# OpenLog_ESP32.net
KiCad netlist of a schematic drawn in EAGLE
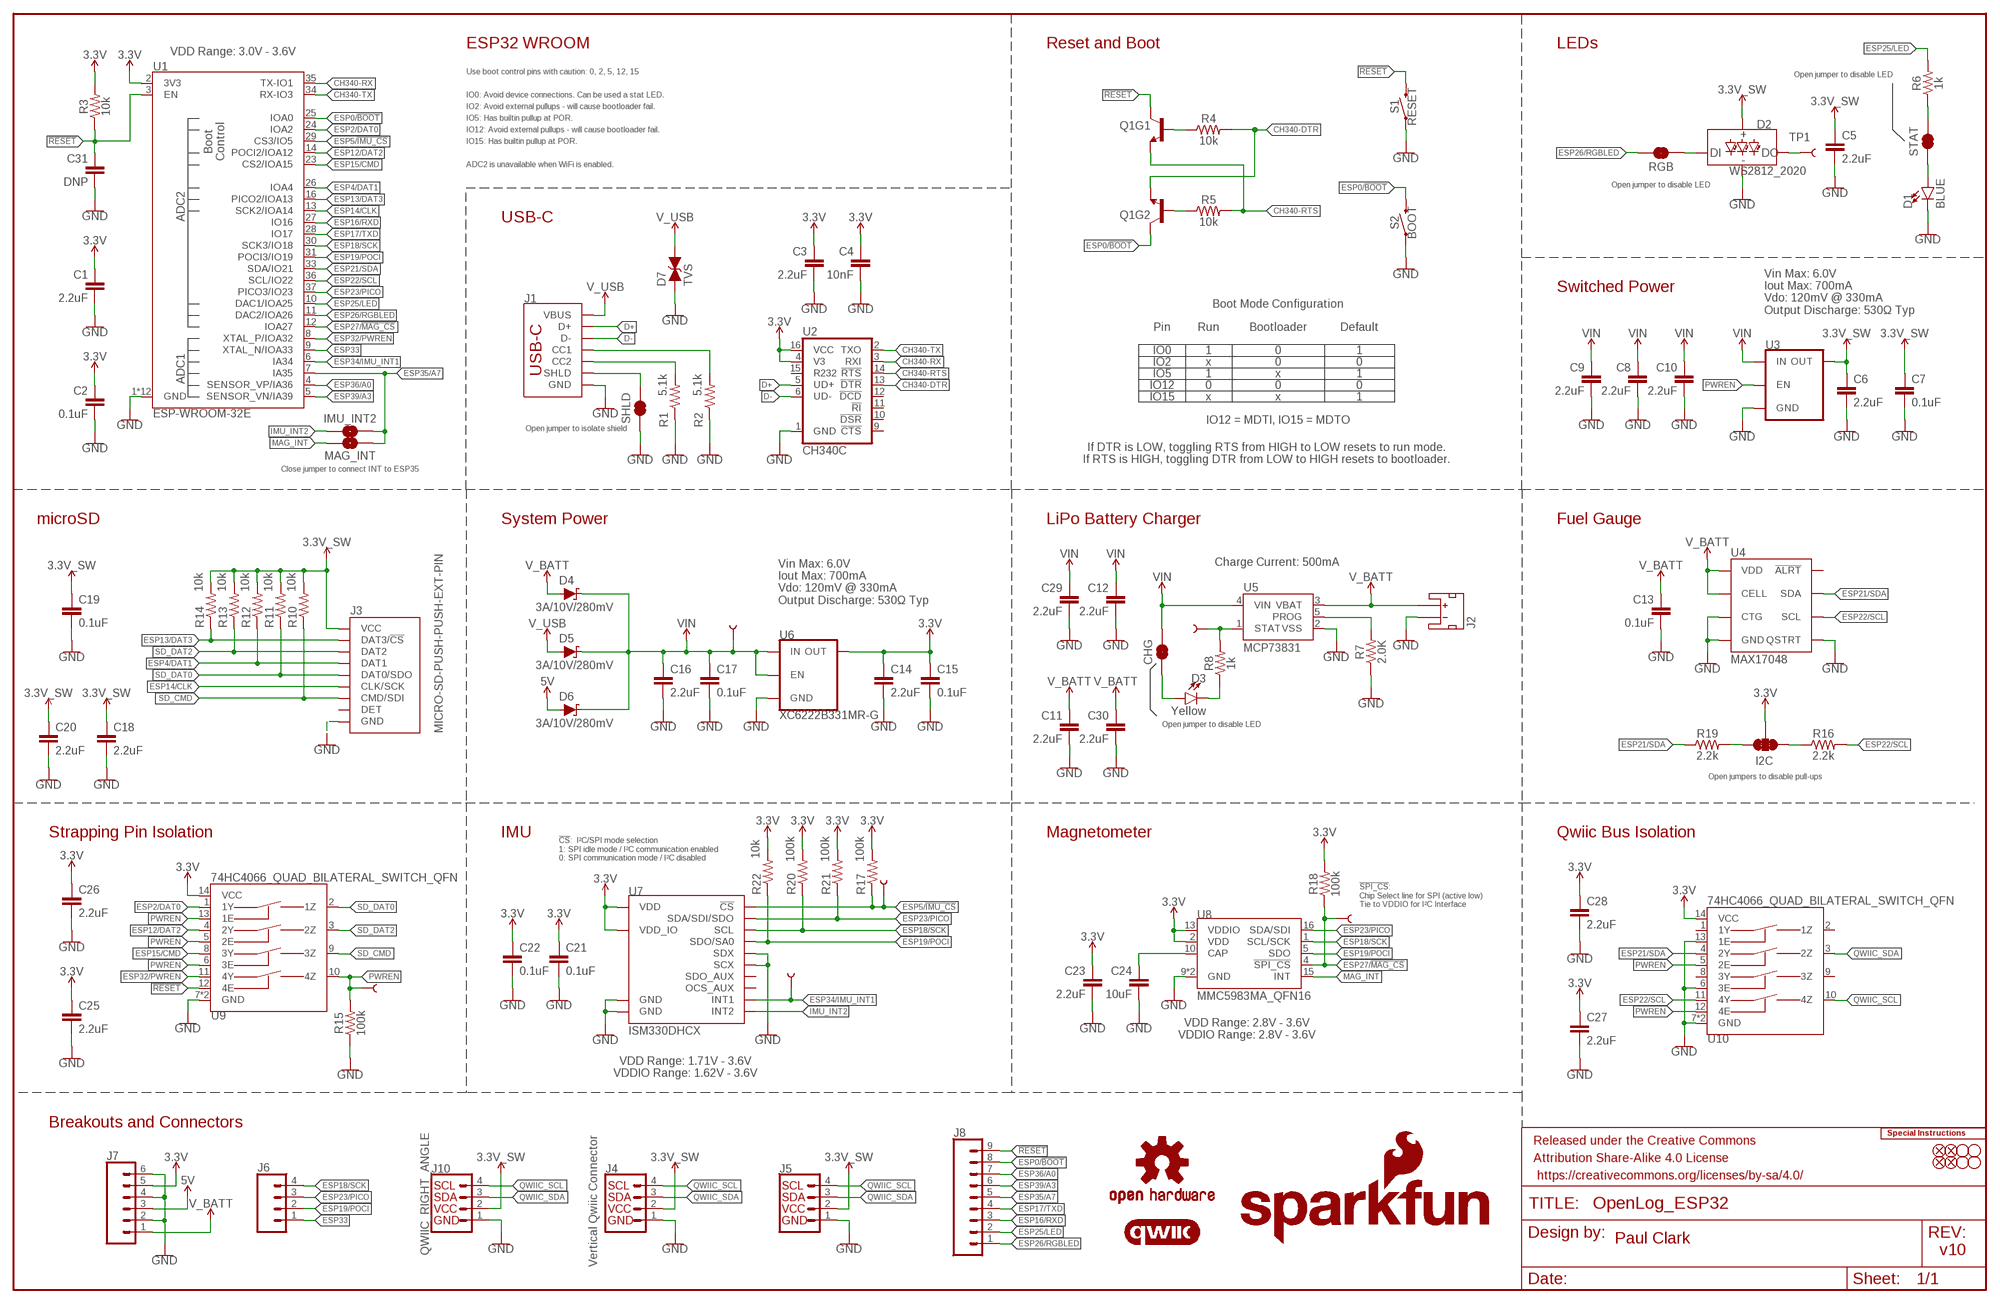
[diagram p0: schematic, sheet 1]

(export (version "E")
  (design (tool "Eeschema 10.0.6"))
  (components
    (comp (ref "C1")
      (value "2.2uF")
      (footprint "eagle-import:0402-TIGHT")
      (libsource (lib "eagle-import") (part "2.2UF-0402_TIGHT-10V-10%-X5R"))
    )
    (comp (ref "C2")
      (value "0.1uF")
      (footprint "eagle-import:0402-TIGHT")
      (libsource (lib "eagle-import") (part "0.1UF-0402T-6.3V-10%-X7R"))
    )
    (comp (ref "C3")
      (value "2.2uF")
      (footprint "eagle-import:0402-TIGHT")
      (libsource (lib "eagle-import") (part "2.2UF-0402_TIGHT-10V-10%-X5R"))
    )
    (comp (ref "C4")
      (value "10nF")
      (footprint "eagle-import:0402-TIGHT")
      (libsource (lib "eagle-import") (part "10NF-0402T-25V-10%-X7R-WE"))
    )
    (comp (ref "C5")
      (value "2.2uF")
      (footprint "eagle-import:0402-TIGHT")
      (libsource (lib "eagle-import") (part "2.2UF-0402_TIGHT-10V-10%-X5R"))
    )
    (comp (ref "C6")
      (value "2.2uF")
      (footprint "eagle-import:0402-TIGHT")
      (libsource (lib "eagle-import") (part "2.2UF-0402_TIGHT-10V-10%-X5R"))
    )
    (comp (ref "C7")
      (value "0.1uF")
      (footprint "eagle-import:0402-TIGHT")
      (libsource (lib "eagle-import") (part "0.1UF-0402T-6.3V-10%-X7R"))
    )
    (comp (ref "C8")
      (value "2.2uF")
      (footprint "eagle-import:0402-TIGHT")
      (libsource (lib "eagle-import") (part "2.2UF-0402_TIGHT-10V-10%-X5R"))
    )
    (comp (ref "C9")
      (value "2.2uF")
      (footprint "eagle-import:0402-TIGHT")
      (libsource (lib "eagle-import") (part "2.2UF-0402_TIGHT-10V-10%-X5R"))
    )
    (comp (ref "C10")
      (value "2.2uF")
      (footprint "eagle-import:0402-TIGHT")
      (libsource (lib "eagle-import") (part "2.2UF-0402_TIGHT-10V-10%-X5R"))
    )
    (comp (ref "C11")
      (value "2.2uF")
      (footprint "eagle-import:0402-TIGHT")
      (libsource (lib "eagle-import") (part "2.2UF-0402_TIGHT-10V-10%-X5R"))
    )
    (comp (ref "C12")
      (value "2.2uF")
      (footprint "eagle-import:0402-TIGHT")
      (libsource (lib "eagle-import") (part "2.2UF-0402_TIGHT-10V-10%-X5R"))
    )
    (comp (ref "C13")
      (value "0.1uF")
      (footprint "eagle-import:0402-TIGHT")
      (libsource (lib "eagle-import") (part "0.1UF-0402T-6.3V-10%-X7R"))
    )
    (comp (ref "C14")
      (value "2.2uF")
      (footprint "eagle-import:0402-TIGHT")
      (libsource (lib "eagle-import") (part "2.2UF-0402_TIGHT-10V-10%-X5R"))
    )
    (comp (ref "C15")
      (value "0.1uF")
      (footprint "eagle-import:0402-TIGHT")
      (libsource (lib "eagle-import") (part "0.1UF-0402T-6.3V-10%-X7R"))
    )
    (comp (ref "C16")
      (value "2.2uF")
      (footprint "eagle-import:0402-TIGHT")
      (libsource (lib "eagle-import") (part "2.2UF-0402_TIGHT-10V-10%-X5R"))
    )
    (comp (ref "C17")
      (value "0.1uF")
      (footprint "eagle-import:0402-TIGHT")
      (libsource (lib "eagle-import") (part "0.1UF-0402T-6.3V-10%-X7R"))
    )
    (comp (ref "C18")
      (value "2.2uF")
      (footprint "eagle-import:0402-TIGHT")
      (libsource (lib "eagle-import") (part "2.2UF-0402_TIGHT-10V-10%-X5R"))
    )
    (comp (ref "C19")
      (value "0.1uF")
      (footprint "eagle-import:0402-TIGHT")
      (libsource (lib "eagle-import") (part "0.1UF-0402T-6.3V-10%-X7R"))
    )
    (comp (ref "C20")
      (value "2.2uF")
      (footprint "eagle-import:0402-TIGHT")
      (libsource (lib "eagle-import") (part "2.2UF-0402_TIGHT-10V-10%-X5R"))
    )
    (comp (ref "C21")
      (value "0.1uF")
      (footprint "eagle-import:0402-TIGHT")
      (libsource (lib "eagle-import") (part "0.1UF-0402T-6.3V-10%-X7R"))
    )
    (comp (ref "C22")
      (value "0.1uF")
      (footprint "eagle-import:0402-TIGHT")
      (libsource (lib "eagle-import") (part "0.1UF-0402T-6.3V-10%-X7R"))
    )
    (comp (ref "C23")
      (value "2.2uF")
      (footprint "eagle-import:0402-TIGHT")
      (libsource (lib "eagle-import") (part "2.2UF-0402_TIGHT-10V-10%-X5R"))
    )
    (comp (ref "C24")
      (value "10uF")
      (footprint "eagle-import:0402-TIGHT")
      (libsource (lib "eagle-import") (part "10UF-0402T-6.3V-20%"))
    )
    (comp (ref "C25")
      (value "2.2uF")
      (footprint "eagle-import:0402-TIGHT")
      (libsource (lib "eagle-import") (part "2.2UF-0402_TIGHT-10V-10%-X5R"))
    )
    (comp (ref "C26")
      (value "2.2uF")
      (footprint "eagle-import:0402-TIGHT")
      (libsource (lib "eagle-import") (part "2.2UF-0402_TIGHT-10V-10%-X5R"))
    )
    (comp (ref "C27")
      (value "2.2uF")
      (footprint "eagle-import:0402-TIGHT")
      (libsource (lib "eagle-import") (part "2.2UF-0402_TIGHT-10V-10%-X5R"))
    )
    (comp (ref "C28")
      (value "2.2uF")
      (footprint "eagle-import:0402-TIGHT")
      (libsource (lib "eagle-import") (part "2.2UF-0402_TIGHT-10V-10%-X5R"))
    )
    (comp (ref "C29")
      (value "2.2uF")
      (footprint "eagle-import:0402-TIGHT")
      (libsource (lib "eagle-import") (part "2.2UF-0402_TIGHT-10V-10%-X5R"))
    )
    (comp (ref "C30")
      (value "2.2uF")
      (footprint "eagle-import:0402-TIGHT")
      (libsource (lib "eagle-import") (part "2.2UF-0402_TIGHT-10V-10%-X5R"))
    )
    (comp (ref "C31")
      (value "DNP")
      (footprint "eagle-import:0402-TIGHT_NO_CREAM")
      (libsource (lib "eagle-import") (part "DNP-0402-TIGHT_NO_CREAM"))
    )
    (comp (ref "CHG")
      (value "JUMPER-SMT_2_NC_TRACE_SILK")
      (footprint "eagle-import:SMT-JUMPER_2_NC_TRACE_SILK")
      (libsource (lib "eagle-import") (part "JUMPER-SMT_2_NC_TRACE_SILK"))
    )
    (comp (ref "D1")
      (value "BLUE")
      (footprint "eagle-import:LED-0603")
      (libsource (lib "eagle-import") (part "LED-BLUE0603"))
    )
    (comp (ref "D2")
      (value "WS2812_2020")
      (footprint "eagle-import:WS2812-2020")
      (libsource (lib "eagle-import") (part "WS2812_2020"))
    )
    (comp (ref "D3")
      (value "Yellow")
      (footprint "eagle-import:LED-0603")
      (libsource (lib "eagle-import") (part "LED-YELLOW0603"))
    )
    (comp (ref "D4")
      (value "3A/10V/280mV")
      (footprint "eagle-import:SOD-323")
      (libsource (lib "eagle-import") (part "DIODE-SCHOTTKY-BAT60A"))
    )
    (comp (ref "D5")
      (value "3A/10V/280mV")
      (footprint "eagle-import:SOD-323")
      (libsource (lib "eagle-import") (part "DIODE-SCHOTTKY-BAT60A"))
    )
    (comp (ref "D6")
      (value "3A/10V/280mV")
      (footprint "eagle-import:SOD-323")
      (libsource (lib "eagle-import") (part "DIODE-SCHOTTKY-BAT60A"))
    )
    (comp (ref "D7")
      (value "TVS")
      (footprint "eagle-import:0603")
      (libsource (lib "eagle-import") (part "DIODE_TVS"))
    )
    (comp (ref "FD1")
      (value "FIDUCIAL1X2")
      (footprint "eagle-import:FIDUCIAL-1X2")
      (libsource (lib "eagle-import") (part "FIDUCIAL1X2"))
    )
    (comp (ref "FD2")
      (value "FIDUCIAL1X2")
      (footprint "eagle-import:FIDUCIAL-1X2")
      (libsource (lib "eagle-import") (part "FIDUCIAL1X2"))
    )
    (comp (ref "FD3")
      (value "FIDUCIAL1X2")
      (footprint "eagle-import:FIDUCIAL-1X2")
      (libsource (lib "eagle-import") (part "FIDUCIAL1X2"))
    )
    (comp (ref "FD4")
      (value "FIDUCIAL1X2")
      (footprint "eagle-import:FIDUCIAL-1X2")
      (libsource (lib "eagle-import") (part "FIDUCIAL1X2"))
    )
    (comp (ref "FRAME1")
      (value "FRAME-LEDGER")
      (footprint "eagle-import:CREATIVE_COMMONS")
      (libsource (lib "eagle-import") (part "FRAME-LEDGER"))
    )
    (comp (ref "H1")
      (value "STAND-OFFTIGHT")
      (footprint "eagle-import:STAND-OFF-TIGHT")
      (libsource (lib "eagle-import") (part "STAND-OFFTIGHT"))
    )
    (comp (ref "H2")
      (value "STAND-OFFTIGHT")
      (footprint "eagle-import:STAND-OFF-TIGHT")
      (libsource (lib "eagle-import") (part "STAND-OFFTIGHT"))
    )
    (comp (ref "H3")
      (value "STAND-OFFTIGHT")
      (footprint "eagle-import:STAND-OFF-TIGHT")
      (libsource (lib "eagle-import") (part "STAND-OFFTIGHT"))
    )
    (comp (ref "H4")
      (value "STAND-OFFTIGHT")
      (footprint "eagle-import:STAND-OFF-TIGHT")
      (libsource (lib "eagle-import") (part "STAND-OFFTIGHT"))
    )
    (comp (ref "I2C")
      (value "JUMPER-SMT_3_2-NC_TRACE_SILK")
      (footprint "eagle-import:SMT-JUMPER_3_2-NC_TRACE_SILK")
      (libsource (lib "eagle-import") (part "JUMPER-SMT_3_2-NC_TRACE_SILK"))
    )
    (comp (ref "IMU_!CS!")
      (value "TEST-POINT3X5")
      (footprint "eagle-import:PAD.03X.05")
      (libsource (lib "eagle-import") (part "TEST-POINT3X5"))
    )
    (comp (ref "IMU_INT1")
      (value "TEST-POINT3X5")
      (footprint "eagle-import:PAD.03X.05")
      (libsource (lib "eagle-import") (part "TEST-POINT3X5"))
    )
    (comp (ref "IMU_INT2")
      (value "JUMPER-SMT_2_NO_SILK")
      (footprint "eagle-import:SMT-JUMPER_2_NO_SILK")
      (libsource (lib "eagle-import") (part "JUMPER-SMT_2_NO_SILK"))
    )
    (comp (ref "J1")
      (value "USB_C_4-LAYER_PADS")
      (footprint "eagle-import:USB-C-16P_4LAYER-PADS")
      (libsource (lib "eagle-import") (part "USB_C_4-LAYER_PADS"))
    )
    (comp (ref "J2")
      (value "JST_2MM_MALE")
      (footprint "eagle-import:JST-2-SMD")
      (libsource (lib "eagle-import") (part "JST_2MM_MALE"))
    )
    (comp (ref "J3")
      (value "MICRO-SD-PUSH-PUSH-EXT-PIN")
      (footprint "eagle-import:MICROSD-EXTERNALPIN")
      (libsource (lib "eagle-import") (part "MICRO-SD-PUSH-PUSH-EXT-PIN"))
    )
    (comp (ref "J4")
      (value "Vertical Qwiic Connector")
      (footprint "eagle-import:JST04_1MM_VERT")
      (libsource (lib "eagle-import") (part "QWIIC_CONNECTOR"))
    )
    (comp (ref "J5")
      (value "I2C_STANDARD_NO_SILK")
      (footprint "eagle-import:1X04_NO_SILK")
      (libsource (lib "eagle-import") (part "I2C_STANDARD_NO_SILK"))
    )
    (comp (ref "J6")
      (value "CONN_041X04_NO_SILK_NO_POP")
      (footprint "eagle-import:1X04_NO_SILK")
      (libsource (lib "eagle-import") (part "CONN_041X04_NO_SILK_NO_POP"))
    )
    (comp (ref "J7")
      (value "CONN_06NO_SILK_NO_POP")
      (footprint "eagle-import:1X06_NO_SILK")
      (libsource (lib "eagle-import") (part "CONN_06NO_SILK_NO_POP"))
    )
    (comp (ref "J8")
      (value "CONN_09NO_SILK")
      (footprint "eagle-import:1X09_NO_SILK")
      (libsource (lib "eagle-import") (part "CONN_09NO_SILK"))
    )
    (comp (ref "J10")
      (value "QWIIC_RIGHT_ANGLE")
      (footprint "eagle-import:JST04_1MM_RA")
      (libsource (lib "eagle-import") (part "QWIIC_CONNECTORJS-1MM"))
    )
    (comp (ref "LOGO1")
      (value "SPECIAL_INSTRUCTIONS-ORDERING")
      (footprint "eagle-import:ORDERING_INSTRUCTIONS")
      (libsource (lib "eagle-import") (part "SPECIAL_INSTRUCTIONS-ORDERING"))
    )
    (comp (ref "LOGO3")
      (value "QWIIC_LOGO_6MM")
      (footprint "eagle-import:QWIIC_6MM")
      (libsource (lib "eagle-import") (part "QWIIC_LOGO_6MM"))
    )
    (comp (ref "LOGO4")
      (value "OSHW-LOGOS")
      (footprint "eagle-import:OSHW-LOGO-S")
      (libsource (lib "eagle-import") (part "OSHW-LOGOS"))
    )
    (comp (ref "LOGO5")
      (value "SFE_LOGO_NAME.2_INCH")
      (footprint "eagle-import:SFE_LOGO_NAME_.2")
      (libsource (lib "eagle-import") (part "SFE_LOGO_NAME.2_INCH"))
    )
    (comp (ref "LOGO6")
      (value "SFE_LOGO_FLAME.2_INCH")
      (footprint "eagle-import:SFE_LOGO_FLAME_.2")
      (libsource (lib "eagle-import") (part "SFE_LOGO_FLAME.2_INCH"))
    )
    (comp (ref "MAG_!CS!")
      (value "TEST-POINT3X5")
      (footprint "eagle-import:PAD.03X.05")
      (libsource (lib "eagle-import") (part "TEST-POINT3X5"))
    )
    (comp (ref "MAG_INT")
      (value "JUMPER-SMT_2_NO_SILK")
      (footprint "eagle-import:SMT-JUMPER_2_NO_SILK")
      (libsource (lib "eagle-import") (part "JUMPER-SMT_2_NO_SILK"))
    )
    (comp (ref "PWREN")
      (value "TEST-POINT3X5")
      (footprint "eagle-import:PAD.03X.05")
      (libsource (lib "eagle-import") (part "TEST-POINT3X5"))
    )
    (comp (ref "Q1")
      (value "TRANS_NPN_DUAL-MBT3904DW1T1")
      (footprint "eagle-import:SC70-6")
      (libsource (lib "eagle-import") (part "TRANS_NPN_DUAL-MBT3904DW1T1"))
    )
    (comp (ref "R1")
      (value "5.1k")
      (footprint "eagle-import:0402-TIGHT")
      (libsource (lib "eagle-import") (part "5.1KOHM-0402T-1/16W-1%"))
    )
    (comp (ref "R2")
      (value "5.1k")
      (footprint "eagle-import:0402-TIGHT")
      (libsource (lib "eagle-import") (part "5.1KOHM-0402T-1/16W-1%"))
    )
    (comp (ref "R3")
      (value "10k")
      (footprint "eagle-import:0402-TIGHT")
      (libsource (lib "eagle-import") (part "10KOHM-0402T-1/16W-1%"))
    )
    (comp (ref "R4")
      (value "10k")
      (footprint "eagle-import:0402-TIGHT")
      (libsource (lib "eagle-import") (part "10KOHM-0402T-1/16W-1%"))
    )
    (comp (ref "R5")
      (value "10k")
      (footprint "eagle-import:0402-TIGHT")
      (libsource (lib "eagle-import") (part "10KOHM-0402T-1/16W-1%"))
    )
    (comp (ref "R6")
      (value "1k")
      (footprint "eagle-import:0402-TIGHT")
      (libsource (lib "eagle-import") (part "1KOHM-0402T-1/16W-1%"))
    )
    (comp (ref "R7")
      (value "2.0K")
      (footprint "eagle-import:0402-TIGHT")
      (libsource (lib "eagle-import") (part "2.0KOHM-0402T-1/16W-1%"))
    )
    (comp (ref "R8")
      (value "1k")
      (footprint "eagle-import:0402-TIGHT")
      (libsource (lib "eagle-import") (part "1KOHM-0402T-1/16W-1%"))
    )
    (comp (ref "R10")
      (value "10k")
      (footprint "eagle-import:0402-TIGHT")
      (libsource (lib "eagle-import") (part "10KOHM-0402T-1/16W-1%"))
    )
    (comp (ref "R11")
      (value "10k")
      (footprint "eagle-import:0402-TIGHT")
      (libsource (lib "eagle-import") (part "10KOHM-0402T-1/16W-1%"))
    )
    (comp (ref "R12")
      (value "10k")
      (footprint "eagle-import:0402-TIGHT")
      (libsource (lib "eagle-import") (part "10KOHM-0402T-1/16W-1%"))
    )
    (comp (ref "R13")
      (value "10k")
      (footprint "eagle-import:0402-TIGHT")
      (libsource (lib "eagle-import") (part "10KOHM-0402T-1/16W-1%"))
    )
    (comp (ref "R14")
      (value "10k")
      (footprint "eagle-import:0402-TIGHT")
      (libsource (lib "eagle-import") (part "10KOHM-0402T-1/16W-1%"))
    )
    (comp (ref "R15")
      (value "100k")
      (footprint "eagle-import:0402-TIGHT")
      (libsource (lib "eagle-import") (part "100KOHM-0402T-1/16W-1%"))
    )
    (comp (ref "R16")
      (value "2.2k")
      (footprint "eagle-import:0402-TIGHT")
      (libsource (lib "eagle-import") (part "2.2KOHM-0402T-1/16W-1%"))
    )
    (comp (ref "R17")
      (value "100k")
      (footprint "eagle-import:0402-TIGHT")
      (libsource (lib "eagle-import") (part "100KOHM-0402T-1/16W-1%"))
    )
    (comp (ref "R18")
      (value "100k")
      (footprint "eagle-import:0402-TIGHT")
      (libsource (lib "eagle-import") (part "100KOHM-0402T-1/16W-1%"))
    )
    (comp (ref "R19")
      (value "2.2k")
      (footprint "eagle-import:0402-TIGHT")
      (libsource (lib "eagle-import") (part "2.2KOHM-0402T-1/16W-1%"))
    )
    (comp (ref "R20")
      (value "100k")
      (footprint "eagle-import:0402-TIGHT")
      (libsource (lib "eagle-import") (part "100KOHM-0402T-1/16W-1%"))
    )
    (comp (ref "R21")
      (value "100k")
      (footprint "eagle-import:0402-TIGHT")
      (libsource (lib "eagle-import") (part "100KOHM-0402T-1/16W-1%"))
    )
    (comp (ref "R22")
      (value "10k")
      (footprint "eagle-import:0402-TIGHT")
      (libsource (lib "eagle-import") (part "10KOHM-0402T-1/16W-1%"))
    )
    (comp (ref "RGB")
      (value "JUMPER-SMT_2_NC_TRACE_SILK")
      (footprint "eagle-import:SMT-JUMPER_2_NC_TRACE_SILK")
      (libsource (lib "eagle-import") (part "JUMPER-SMT_2_NC_TRACE_SILK"))
    )
    (comp (ref "S1")
      (value "RESET")
      (footprint "eagle-import:TACTILE_SWITCH_SMD_RIGHT_ANGLE")
      (libsource (lib "eagle-import") (part "MOMENTARY-SWITCH-SPST-SMD-RIGHT-ANGLE"))
    )
    (comp (ref "S2")
      (value "BOOT")
      (footprint "eagle-import:TACTILE_SWITCH_SMD_RIGHT_ANGLE")
      (libsource (lib "eagle-import") (part "MOMENTARY-SWITCH-SPST-SMD-RIGHT-ANGLE"))
    )
    (comp (ref "SHLD")
      (value "JUMPER-SMT_2_NC_TRACE_SILK")
      (footprint "eagle-import:SMT-JUMPER_2_NC_TRACE_SILK")
      (libsource (lib "eagle-import") (part "JUMPER-SMT_2_NC_TRACE_SILK"))
    )
    (comp (ref "STAT")
      (value "JUMPER-SMT_2_NC_TRACE_SILK")
      (footprint "eagle-import:SMT-JUMPER_2_NC_TRACE_SILK")
      (libsource (lib "eagle-import") (part "JUMPER-SMT_2_NC_TRACE_SILK"))
    )
    (comp (ref "TP1")
      (value "TEST-POINT3X5")
      (footprint "eagle-import:PAD.03X.05")
      (libsource (lib "eagle-import") (part "TEST-POINT3X5"))
    )
    (comp (ref "U1")
      (value "ESP-WROOM-32E")
      (footprint "eagle-import:ESP-WROOM-32D-NARROW")
      (libsource (lib "eagle-import") (part "ESP-WROOM-3232D-NARROW"))
    )
    (comp (ref "U2")
      (value "CH340C")
      (footprint "eagle-import:SO016")
      (libsource (lib "eagle-import") (part "CH340C"))
    )
    (comp (ref "U3")
      (value "XC6222B331MR-G")
      (footprint "eagle-import:SOT23-5")
      (libsource (lib "eagle-import") (part "XC6222B331MR-G"))
    )
    (comp (ref "U4")
      (value "MAX17048")
      (footprint "eagle-import:DFN-8")
      (libsource (lib "eagle-import") (part "MAX17048DFN8"))
    )
    (comp (ref "U5")
      (value "MCP73831")
      (footprint "eagle-import:SOT23-5")
      (libsource (lib "eagle-import") (part "MCP73831"))
    )
    (comp (ref "U6")
      (value "XC6222B331MR-G")
      (footprint "eagle-import:SOT23-5")
      (libsource (lib "eagle-import") (part "XC6222B331MR-G"))
    )
    (comp (ref "U7")
      (value "ISM330DHCX")
      (footprint "eagle-import:LGA-14L")
      (libsource (lib "eagle-import") (part "ISM330DHCX"))
    )
    (comp (ref "U8")
      (value "MMC5983MA_QFN16")
      (footprint "eagle-import:LGA-16-3X3MM-4X4PINS")
      (libsource (lib "eagle-import") (part "MMC5983MA_QFN16"))
    )
    (comp (ref "U9")
      (value "74HC4066_QUAD_BILATERAL_SWITCH_QFN")
      (footprint "eagle-import:14-QFN")
      (libsource (lib "eagle-import") (part "74HC4066_QUAD_BILATERAL_SWITCH_QFN"))
    )
    (comp (ref "U10")
      (value "74HC4066_QUAD_BILATERAL_SWITCH_QFN")
      (footprint "eagle-import:14-QFN")
      (libsource (lib "eagle-import") (part "74HC4066_QUAD_BILATERAL_SWITCH_QFN"))
    )
    (comp (ref "VIN")
      (value "TEST-POINT3X5")
      (footprint "eagle-import:PAD.03X.05")
      (libsource (lib "eagle-import") (part "TEST-POINT3X5"))
    )
    (comp (ref "VIN1")
      (value "TEST-POINT3X5")
      (footprint "eagle-import:PAD.03X.05")
      (libsource (lib "eagle-import") (part "TEST-POINT3X5"))
    )
  )
  (nets
    (net (code "1") (name "/ESP0{slash}~{BOOT}") (class "Default")
      (node (ref "J8") (pin "8") (pinfunction "8_8") (pintype "passive"))
      (node (ref "Q1") (pin "6") (pinfunction "C_6") (pintype "passive"))
      (node (ref "S2") (pin "2") (pinfunction "2_2") (pintype "passive"))
      (node (ref "U1") (pin "25") (pinfunction "IOA0_25") (pintype "bidirectional"))
    )
    (net (code "2") (name "/ESP5{slash}~{IMU_CS}") (class "Default")
      (node (ref "IMU_!CS!") (pin "1") (pinfunction "1_1") (pintype "bidirectional"))
      (node (ref "R17") (pin "1") (pinfunction "1_1") (pintype "passive"))
      (node (ref "U1") (pin "29") (pinfunction "CS3/IO5_29") (pintype "bidirectional"))
      (node (ref "U7") (pin "P12") (pinfunction "~{CS}_P12") (pintype "bidirectional"))
    )
    (net (code "3") (name "/ESP27{slash}~{MAG_CS}") (class "Default")
      (node (ref "MAG_!CS!") (pin "1") (pinfunction "1_1") (pintype "bidirectional"))
      (node (ref "R18") (pin "1") (pinfunction "1_1") (pintype "passive"))
      (node (ref "U1") (pin "12") (pinfunction "IOA27_12") (pintype "bidirectional"))
      (node (ref "U8") (pin "4") (pinfunction "~{SPI_CS}_4") (pintype "input"))
    )
    (net (code "4") (name "/~{RESET}") (class "Default")
      (node (ref "C31") (pin "1") (pinfunction "1_1") (pintype "passive"))
      (node (ref "J8") (pin "9") (pinfunction "9_9") (pintype "passive"))
      (node (ref "Q1") (pin "3") (pinfunction "C_3") (pintype "passive"))
      (node (ref "R3") (pin "1") (pinfunction "1_1") (pintype "passive"))
      (node (ref "S1") (pin "2") (pinfunction "2_2") (pintype "passive"))
      (node (ref "U1") (pin "3") (pinfunction "EN_3") (pintype "bidirectional"))
      (node (ref "U9") (pin "12") (pinfunction "4E_12") (pintype "bidirectional"))
    )
    (net (code "5") (name "3.3V") (class "Default")
      (node (ref "C1") (pin "1") (pinfunction "1_1") (pintype "passive"))
      (node (ref "C14") (pin "1") (pinfunction "1_1") (pintype "passive"))
      (node (ref "C15") (pin "1") (pinfunction "1_1") (pintype "passive"))
      (node (ref "C2") (pin "1") (pinfunction "1_1") (pintype "passive"))
      (node (ref "C21") (pin "1") (pinfunction "1_1") (pintype "passive"))
      (node (ref "C22") (pin "1") (pinfunction "1_1") (pintype "passive"))
      (node (ref "C23") (pin "1") (pinfunction "1_1") (pintype "passive"))
      (node (ref "C25") (pin "1") (pinfunction "1_1") (pintype "passive"))
      (node (ref "C26") (pin "1") (pinfunction "1_1") (pintype "passive"))
      (node (ref "C27") (pin "1") (pinfunction "1_1") (pintype "passive"))
      (node (ref "C28") (pin "1") (pinfunction "1_1") (pintype "passive"))
      (node (ref "C3") (pin "1") (pinfunction "1_1") (pintype "passive"))
      (node (ref "C4") (pin "1") (pinfunction "1_1") (pintype "passive"))
      (node (ref "I2C") (pin "2") (pinfunction "2_2") (pintype "passive"))
      (node (ref "J7") (pin "5") (pinfunction "5_5") (pintype "passive"))
      (node (ref "R17") (pin "2") (pinfunction "2_2") (pintype "passive"))
      (node (ref "R18") (pin "2") (pinfunction "2_2") (pintype "passive"))
      (node (ref "R20") (pin "2") (pinfunction "2_2") (pintype "passive"))
      (node (ref "R21") (pin "2") (pinfunction "2_2") (pintype "passive"))
      (node (ref "R22") (pin "2") (pinfunction "2_2") (pintype "passive"))
      (node (ref "R3") (pin "2") (pinfunction "2_2") (pintype "passive"))
      (node (ref "U1") (pin "2") (pinfunction "3V3_2") (pintype "bidirectional"))
      (node (ref "U10") (pin "14") (pinfunction "VCC_14") (pintype "bidirectional"))
      (node (ref "U2") (pin "16") (pinfunction "VCC_16") (pintype "bidirectional"))
      (node (ref "U2") (pin "4") (pinfunction "V3_4") (pintype "bidirectional"))
      (node (ref "U6") (pin "5") (pinfunction "OUT_5") (pintype "passive"))
      (node (ref "U7") (pin "P5") (pinfunction "VDD_IO_P5") (pintype "power_in"))
      (node (ref "U7") (pin "P8") (pinfunction "VDD_P8") (pintype "power_in"))
      (node (ref "U8") (pin "13") (pinfunction "VDDIO_13") (pintype "power_in"))
      (node (ref "U8") (pin "2") (pinfunction "VDD_2") (pintype "power_in"))
      (node (ref "U9") (pin "14") (pinfunction "VCC_14") (pintype "bidirectional"))
    )
    (net (code "6") (name "3.3V_SW") (class "Default")
      (node (ref "C18") (pin "1") (pinfunction "1_1") (pintype "passive"))
      (node (ref "C19") (pin "1") (pinfunction "1_1") (pintype "passive"))
      (node (ref "C20") (pin "1") (pinfunction "1_1") (pintype "passive"))
      (node (ref "C5") (pin "1") (pinfunction "1_1") (pintype "passive"))
      (node (ref "C6") (pin "1") (pinfunction "1_1") (pintype "passive"))
      (node (ref "C7") (pin "1") (pinfunction "1_1") (pintype "passive"))
      (node (ref "D2") (pin "VCC") (pinfunction "VCC_VCC") (pintype "bidirectional"))
      (node (ref "J10") (pin "2") (pinfunction "2_2") (pintype "power_in"))
      (node (ref "J3") (pin "4") (pinfunction "VCC_4") (pintype "bidirectional"))
      (node (ref "J4") (pin "2") (pinfunction "2_2") (pintype "power_in"))
      (node (ref "J5") (pin "2") (pinfunction "2_2") (pintype "power_in"))
      (node (ref "R10") (pin "2") (pinfunction "2_2") (pintype "passive"))
      (node (ref "R11") (pin "2") (pinfunction "2_2") (pintype "passive"))
      (node (ref "R12") (pin "2") (pinfunction "2_2") (pintype "passive"))
      (node (ref "R13") (pin "2") (pinfunction "2_2") (pintype "passive"))
      (node (ref "R14") (pin "2") (pinfunction "2_2") (pintype "passive"))
      (node (ref "U3") (pin "5") (pinfunction "OUT_5") (pintype "passive"))
    )
    (net (code "7") (name "5V") (class "Default")
      (node (ref "D6") (pin "A") (pinfunction "A_A") (pintype "passive"))
      (node (ref "J7") (pin "3") (pinfunction "3_3") (pintype "passive"))
    )
    (net (code "8") (name "CH340-DTR") (class "Default")
      (node (ref "Q1") (pin "1") (pinfunction "E_1") (pintype "passive"))
      (node (ref "R4") (pin "2") (pinfunction "2_2") (pintype "passive"))
      (node (ref "U2") (pin "13") (pinfunction "~{DTR}_13") (pintype "bidirectional"))
    )
    (net (code "9") (name "CH340-RTS") (class "Default")
      (node (ref "Q1") (pin "4") (pinfunction "E_4") (pintype "passive"))
      (node (ref "R5") (pin "2") (pinfunction "2_2") (pintype "passive"))
      (node (ref "U2") (pin "14") (pinfunction "~{RTS}_14") (pintype "bidirectional"))
    )
    (net (code "10") (name "CH340-RX") (class "Default")
      (node (ref "U1") (pin "35") (pinfunction "TX-IO1_35") (pintype "bidirectional"))
      (node (ref "U2") (pin "3") (pinfunction "RXI_3") (pintype "bidirectional"))
    )
    (net (code "11") (name "CH340-TX") (class "Default")
      (node (ref "U1") (pin "34") (pinfunction "RX-IO3_34") (pintype "bidirectional"))
      (node (ref "U2") (pin "2") (pinfunction "TXO_2") (pintype "bidirectional"))
    )
    (net (code "12") (name "D+") (class "Default")
      (node (ref "J1") (pin "A6") (pinfunction "D+_A6") (pintype "bidirectional"))
      (node (ref "J1") (pin "B6") (pinfunction "D+_B6") (pintype "bidirectional"))
      (node (ref "U2") (pin "5") (pinfunction "UD+_5") (pintype "bidirectional"))
    )
    (net (code "13") (name "D-") (class "Default")
      (node (ref "J1") (pin "A7") (pinfunction "D-_A7") (pintype "bidirectional"))
      (node (ref "J1") (pin "B7") (pinfunction "D-_B7") (pintype "bidirectional"))
      (node (ref "U2") (pin "6") (pinfunction "UD-_6") (pintype "bidirectional"))
    )
    (net (code "14") (name "ESP2{slash}DAT0") (class "Default")
      (node (ref "U1") (pin "24") (pinfunction "IOA2_24") (pintype "bidirectional"))
      (node (ref "U9") (pin "1") (pinfunction "1Y_1") (pintype "bidirectional"))
    )
    (net (code "15") (name "ESP4{slash}DAT1") (class "Default")
      (node (ref "J3") (pin "8") (pinfunction "DAT1_8") (pintype "bidirectional"))
      (node (ref "R12") (pin "1") (pinfunction "1_1") (pintype "passive"))
      (node (ref "U1") (pin "26") (pinfunction "IOA4_26") (pintype "bidirectional"))
    )
    (net (code "16") (name "ESP12{slash}DAT2") (class "Default")
      (node (ref "U1") (pin "14") (pinfunction "POCI2/IOA12_14") (pintype "bidirectional"))
      (node (ref "U9") (pin "4") (pinfunction "2Y_4") (pintype "bidirectional"))
    )
    (net (code "17") (name "ESP13{slash}DAT3") (class "Default")
      (node (ref "J3") (pin "2") (pinfunction "DAT3/~{CS}_2") (pintype "bidirectional"))
      (node (ref "R14") (pin "1") (pinfunction "1_1") (pintype "passive"))
      (node (ref "U1") (pin "16") (pinfunction "PICO2/IOA13_16") (pintype "bidirectional"))
    )
    (net (code "18") (name "ESP14{slash}CLK") (class "Default")
      (node (ref "J3") (pin "5") (pinfunction "CLK/SCK_5") (pintype "bidirectional"))
      (node (ref "U1") (pin "13") (pinfunction "SCK2/IOA14_13") (pintype "bidirectional"))
    )
    (net (code "19") (name "ESP15{slash}CMD") (class "Default")
      (node (ref "U1") (pin "23") (pinfunction "CS2/IOA15_23") (pintype "bidirectional"))
      (node (ref "U9") (pin "8") (pinfunction "3Y_8") (pintype "bidirectional"))
    )
    (net (code "20") (name "ESP16{slash}RXD") (class "Default")
      (node (ref "J8") (pin "3") (pinfunction "3_3") (pintype "passive"))
      (node (ref "U1") (pin "27") (pinfunction "IO16_27") (pintype "bidirectional"))
    )
    (net (code "21") (name "ESP17{slash}TXD") (class "Default")
      (node (ref "J8") (pin "4") (pinfunction "4_4") (pintype "passive"))
      (node (ref "U1") (pin "28") (pinfunction "IO17_28") (pintype "bidirectional"))
    )
    (net (code "22") (name "ESP18{slash}SCK") (class "Default")
      (node (ref "J6") (pin "4") (pinfunction "4_4") (pintype "passive"))
      (node (ref "R20") (pin "1") (pinfunction "1_1") (pintype "passive"))
      (node (ref "U1") (pin "30") (pinfunction "SCK3/IO18_30") (pintype "bidirectional"))
      (node (ref "U7") (pin "P13") (pinfunction "SCL_P13") (pintype "bidirectional"))
      (node (ref "U8") (pin "1") (pinfunction "SCL/SCK_1") (pintype "bidirectional"))
    )
    (net (code "23") (name "ESP19{slash}POCI") (class "Default")
      (node (ref "J6") (pin "2") (pinfunction "2_2") (pintype "passive"))
      (node (ref "R22") (pin "1") (pinfunction "1_1") (pintype "passive"))
      (node (ref "U1") (pin "31") (pinfunction "POCI3/IO19_31") (pintype "bidirectional"))
      (node (ref "U7") (pin "P1") (pinfunction "SDO/SA0_P1") (pintype "bidirectional"))
      (node (ref "U8") (pin "5") (pinfunction "SDO_5") (pintype "output"))
    )
    (net (code "24") (name "ESP21{slash}SDA") (class "Default")
      (node (ref "R19") (pin "1") (pinfunction "1_1") (pintype "passive"))
      (node (ref "U1") (pin "33") (pinfunction "SDA/IO21_33") (pintype "bidirectional"))
      (node (ref "U10") (pin "4") (pinfunction "2Y_4") (pintype "bidirectional"))
      (node (ref "U4") (pin "8") (pinfunction "SDA_8") (pintype "input"))
    )
    (net (code "25") (name "ESP22{slash}SCL") (class "Default")
      (node (ref "R16") (pin "2") (pinfunction "2_2") (pintype "passive"))
      (node (ref "U1") (pin "36") (pinfunction "SCL/IO22_36") (pintype "bidirectional"))
      (node (ref "U10") (pin "11") (pinfunction "4Y_11") (pintype "bidirectional"))
      (node (ref "U4") (pin "7") (pinfunction "SCL_7") (pintype "output"))
    )
    (net (code "26") (name "ESP23{slash}PICO") (class "Default")
      (node (ref "J6") (pin "3") (pinfunction "3_3") (pintype "passive"))
      (node (ref "R21") (pin "1") (pinfunction "1_1") (pintype "passive"))
      (node (ref "U1") (pin "37") (pinfunction "PICO3/IO23_37") (pintype "bidirectional"))
      (node (ref "U7") (pin "P14") (pinfunction "SDA/SDI/SDO_P14") (pintype "bidirectional"))
      (node (ref "U8") (pin "16") (pinfunction "SDA/SDI_16") (pintype "bidirectional"))
    )
    (net (code "27") (name "ESP25{slash}LED") (class "Default")
      (node (ref "J8") (pin "2") (pinfunction "2_2") (pintype "passive"))
      (node (ref "R6") (pin "2") (pinfunction "2_2") (pintype "passive"))
      (node (ref "U1") (pin "10") (pinfunction "DAC1/IOA25_10") (pintype "bidirectional"))
    )
    (net (code "28") (name "ESP26{slash}RGBLED") (class "Default")
      (node (ref "J8") (pin "1") (pinfunction "1_1") (pintype "passive"))
      (node (ref "RGB") (pin "2") (pinfunction "2_2") (pintype "passive"))
      (node (ref "U1") (pin "11") (pinfunction "DAC2/IOA26_11") (pintype "bidirectional"))
    )
    (net (code "29") (name "ESP32{slash}PWREN") (class "Default")
      (node (ref "U1") (pin "8") (pinfunction "XTAL_P/IOA32_8") (pintype "bidirectional"))
      (node (ref "U9") (pin "11") (pinfunction "4Y_11") (pintype "bidirectional"))
    )
    (net (code "30") (name "ESP33") (class "Default")
      (node (ref "J6") (pin "1") (pinfunction "1_1") (pintype "passive"))
      (node (ref "U1") (pin "9") (pinfunction "XTAL_N/IOA33_9") (pintype "bidirectional"))
    )
    (net (code "31") (name "ESP34{slash}IMU_INT1") (class "Default")
      (node (ref "IMU_INT1") (pin "1") (pinfunction "1_1") (pintype "bidirectional"))
      (node (ref "U1") (pin "6") (pinfunction "IA34_6") (pintype "bidirectional"))
      (node (ref "U7") (pin "P4") (pinfunction "INT1_P4") (pintype "bidirectional"))
    )
    (net (code "32") (name "ESP35{slash}A7") (class "Default")
      (node (ref "IMU_INT2") (pin "2") (pinfunction "2_2") (pintype "passive"))
      (node (ref "J8") (pin "5") (pinfunction "5_5") (pintype "passive"))
      (node (ref "MAG_INT") (pin "2") (pinfunction "2_2") (pintype "passive"))
      (node (ref "U1") (pin "7") (pinfunction "IA35_7") (pintype "bidirectional"))
    )
    (net (code "33") (name "ESP36{slash}A0") (class "Default")
      (node (ref "J8") (pin "7") (pinfunction "7_7") (pintype "passive"))
      (node (ref "U1") (pin "4") (pinfunction "SENSOR_VP/IA36_4") (pintype "bidirectional"))
    )
    (net (code "34") (name "ESP39{slash}A3") (class "Default")
      (node (ref "J8") (pin "6") (pinfunction "6_6") (pintype "passive"))
      (node (ref "U1") (pin "5") (pinfunction "SENSOR_VN/IA39_5") (pintype "bidirectional"))
    )
    (net (code "35") (name "GND") (class "Default")
      (node (ref "C1") (pin "2") (pinfunction "2_2") (pintype "passive"))
      (node (ref "C10") (pin "2") (pinfunction "2_2") (pintype "passive"))
      (node (ref "C11") (pin "2") (pinfunction "2_2") (pintype "passive"))
      (node (ref "C12") (pin "2") (pinfunction "2_2") (pintype "passive"))
      (node (ref "C13") (pin "2") (pinfunction "2_2") (pintype "passive"))
      (node (ref "C14") (pin "2") (pinfunction "2_2") (pintype "passive"))
      (node (ref "C15") (pin "2") (pinfunction "2_2") (pintype "passive"))
      (node (ref "C16") (pin "2") (pinfunction "2_2") (pintype "passive"))
      (node (ref "C17") (pin "2") (pinfunction "2_2") (pintype "passive"))
      (node (ref "C18") (pin "2") (pinfunction "2_2") (pintype "passive"))
      (node (ref "C19") (pin "2") (pinfunction "2_2") (pintype "passive"))
      (node (ref "C2") (pin "2") (pinfunction "2_2") (pintype "passive"))
      (node (ref "C20") (pin "2") (pinfunction "2_2") (pintype "passive"))
      (node (ref "C21") (pin "2") (pinfunction "2_2") (pintype "passive"))
      (node (ref "C22") (pin "2") (pinfunction "2_2") (pintype "passive"))
      (node (ref "C23") (pin "2") (pinfunction "2_2") (pintype "passive"))
      (node (ref "C24") (pin "2") (pinfunction "2_2") (pintype "passive"))
      (node (ref "C25") (pin "2") (pinfunction "2_2") (pintype "passive"))
      (node (ref "C26") (pin "2") (pinfunction "2_2") (pintype "passive"))
      (node (ref "C27") (pin "2") (pinfunction "2_2") (pintype "passive"))
      (node (ref "C28") (pin "2") (pinfunction "2_2") (pintype "passive"))
      (node (ref "C29") (pin "2") (pinfunction "2_2") (pintype "passive"))
      (node (ref "C3") (pin "2") (pinfunction "2_2") (pintype "passive"))
      (node (ref "C30") (pin "2") (pinfunction "2_2") (pintype "passive"))
      (node (ref "C31") (pin "2") (pinfunction "2_2") (pintype "passive"))
      (node (ref "C4") (pin "2") (pinfunction "2_2") (pintype "passive"))
      (node (ref "C5") (pin "2") (pinfunction "2_2") (pintype "passive"))
      (node (ref "C6") (pin "2") (pinfunction "2_2") (pintype "passive"))
      (node (ref "C7") (pin "2") (pinfunction "2_2") (pintype "passive"))
      (node (ref "C8") (pin "2") (pinfunction "2_2") (pintype "passive"))
      (node (ref "C9") (pin "2") (pinfunction "2_2") (pintype "passive"))
      (node (ref "D1") (pin "C") (pinfunction "C_C") (pintype "passive"))
      (node (ref "D2") (pin "GND") (pinfunction "GND_GND") (pintype "bidirectional"))
      (node (ref "D7") (pin "1") (pinfunction "A_1") (pintype "passive"))
      (node (ref "J1") (pin "GND") (pinfunction "GND_GND") (pintype "bidirectional"))
      (node (ref "J1") (pin "GND2") (pinfunction "GND_GND2") (pintype "bidirectional"))
      (node (ref "J10") (pin "1") (pinfunction "1_1") (pintype "power_in"))
      (node (ref "J2") (pin "1") (pinfunction "-_1") (pintype "bidirectional"))
      (node (ref "J3") (pin "10") (pinfunction "GND_10") (pintype "bidirectional"))
      (node (ref "J3") (pin "11") (pinfunction "GND_11") (pintype "bidirectional"))
      (node (ref "J3") (pin "12") (pinfunction "GND_12") (pintype "bidirectional"))
      (node (ref "J3") (pin "13") (pinfunction "GND_13") (pintype "bidirectional"))
      (node (ref "J3") (pin "6") (pinfunction "GND_6") (pintype "bidirectional"))
      (node (ref "J4") (pin "1") (pinfunction "1_1") (pintype "power_in"))
      (node (ref "J5") (pin "1") (pinfunction "1_1") (pintype "power_in"))
      (node (ref "J7") (pin "2") (pinfunction "2_2") (pintype "passive"))
      (node (ref "J7") (pin "4") (pinfunction "4_4") (pintype "passive"))
      (node (ref "J7") (pin "6") (pinfunction "6_6") (pintype "passive"))
      (node (ref "R1") (pin "1") (pinfunction "1_1") (pintype "passive"))
      (node (ref "R15") (pin "1") (pinfunction "1_1") (pintype "passive"))
      (node (ref "R2") (pin "1") (pinfunction "1_1") (pintype "passive"))
      (node (ref "R7") (pin "1") (pinfunction "1_1") (pintype "passive"))
      (node (ref "S1") (pin "1") (pinfunction "1_1") (pintype "passive"))
      (node (ref "S2") (pin "1") (pinfunction "1_1") (pintype "passive"))
      (node (ref "SHLD") (pin "1") (pinfunction "1_1") (pintype "passive"))
      (node (ref "U1") (pin "1") (pinfunction "GND_1") (pintype "bidirectional"))
      (node (ref "U1") (pin "15") (pinfunction "GND_15") (pintype "bidirectional"))
      (node (ref "U1") (pin "38") (pinfunction "GND_38") (pintype "bidirectional"))
      (node (ref "U1") (pin "GND1") (pinfunction "GND_GND1") (pintype "bidirectional"))
      (node (ref "U1") (pin "GNDT1") (pinfunction "GND_GNDT1") (pintype "bidirectional"))
      (node (ref "U1") (pin "GNDT2") (pinfunction "GND_GNDT2") (pintype "bidirectional"))
      (node (ref "U1") (pin "GNDT3") (pinfunction "GND_GNDT3") (pintype "bidirectional"))
      (node (ref "U1") (pin "GNDT4") (pinfunction "GND_GNDT4") (pintype "bidirectional"))
      (node (ref "U1") (pin "GNDT5") (pinfunction "GND_GNDT5") (pintype "bidirectional"))
      (node (ref "U1") (pin "GNDT6") (pinfunction "GND_GNDT6") (pintype "bidirectional"))
      (node (ref "U1") (pin "GNDT7") (pinfunction "GND_GNDT7") (pintype "bidirectional"))
      (node (ref "U1") (pin "GNDT8") (pinfunction "GND_GNDT8") (pintype "bidirectional"))
      (node (ref "U10") (pin "13") (pinfunction "1E_13") (pintype "bidirectional"))
      (node (ref "U10") (pin "6") (pinfunction "3E_6") (pintype "bidirectional"))
      (node (ref "U10") (pin "7") (pinfunction "GND_7") (pintype "bidirectional"))
      (node (ref "U10") (pin "EPAD") (pinfunction "GND_EPAD") (pintype "bidirectional"))
      (node (ref "U2") (pin "1") (pinfunction "GND_1") (pintype "bidirectional"))
      (node (ref "U3") (pin "2") (pinfunction "GND_2") (pintype "input"))
      (node (ref "U4") (pin "1") (pinfunction "CTG_1") (pintype "input"))
      (node (ref "U4") (pin "4") (pinfunction "GND_4") (pintype "bidirectional"))
      (node (ref "U4") (pin "6") (pinfunction "QSTRT_6") (pintype "bidirectional"))
      (node (ref "U4") (pin "9") (pinfunction "GND_9") (pintype "bidirectional"))
      (node (ref "U5") (pin "2") (pinfunction "VSS_2") (pintype "power_in"))
      (node (ref "U6") (pin "2") (pinfunction "GND_2") (pintype "input"))
      (node (ref "U7") (pin "P2") (pinfunction "SDX_P2") (pintype "bidirectional"))
      (node (ref "U7") (pin "P3") (pinfunction "SCX_P3") (pintype "bidirectional"))
      (node (ref "U7") (pin "P6") (pinfunction "GND_P6") (pintype "power_in"))
      (node (ref "U7") (pin "P7") (pinfunction "GND_P7") (pintype "power_in"))
      (node (ref "U8") (pin "11") (pinfunction "GND_11") (pintype "power_in"))
      (node (ref "U8") (pin "9") (pinfunction "GND_9") (pintype "power_in"))
      (node (ref "U9") (pin "7") (pinfunction "GND_7") (pintype "bidirectional"))
      (node (ref "U9") (pin "EPAD") (pinfunction "GND_EPAD") (pintype "bidirectional"))
    )
    (net (code "36") (name "IMU_INT2") (class "Default")
      (node (ref "IMU_INT2") (pin "1") (pinfunction "1_1") (pintype "passive"))
      (node (ref "U7") (pin "P9") (pinfunction "INT2_P9") (pintype "bidirectional"))
    )
    (net (code "37") (name "MAG_INT") (class "Default")
      (node (ref "MAG_INT") (pin "1") (pinfunction "1_1") (pintype "passive"))
      (node (ref "U8") (pin "15") (pinfunction "INT_15") (pintype "output"))
    )
    (net (code "38") (name "Net-(CHG-Pad1)") (class "Default")
      (node (ref "CHG") (pin "1") (pinfunction "1_1") (pintype "passive"))
      (node (ref "D3") (pin "A") (pinfunction "A_A") (pintype "passive"))
    )
    (net (code "39") (name "Net-(D1-PadA)") (class "Default")
      (node (ref "D1") (pin "A") (pinfunction "A_A") (pintype "passive"))
      (node (ref "STAT") (pin "1") (pinfunction "1_1") (pintype "passive"))
    )
    (net (code "40") (name "Net-(D2-PadDI)") (class "Default")
      (node (ref "D2") (pin "DI") (pinfunction "DI_DI") (pintype "bidirectional"))
      (node (ref "RGB") (pin "1") (pinfunction "1_1") (pintype "passive"))
    )
    (net (code "41") (name "Net-(D2-PadDO)") (class "Default")
      (node (ref "D2") (pin "DO") (pinfunction "DO_DO") (pintype "bidirectional"))
      (node (ref "TP1") (pin "1") (pinfunction "1_1") (pintype "bidirectional"))
    )
    (net (code "42") (name "Net-(D3-PadC)") (class "Default")
      (node (ref "D3") (pin "C") (pinfunction "C_C") (pintype "passive"))
      (node (ref "R8") (pin "1") (pinfunction "1_1") (pintype "passive"))
    )
    (net (code "43") (name "Net-(I2C-Pad1)") (class "Default")
      (node (ref "I2C") (pin "1") (pinfunction "1_1") (pintype "passive"))
      (node (ref "R16") (pin "1") (pinfunction "1_1") (pintype "passive"))
    )
    (net (code "44") (name "Net-(I2C-Pad3)") (class "Default")
      (node (ref "I2C") (pin "3") (pinfunction "3_3") (pintype "passive"))
      (node (ref "R19") (pin "2") (pinfunction "2_2") (pintype "passive"))
    )
    (net (code "45") (name "Net-(J1-CC1)") (class "Default")
      (node (ref "J1") (pin "A5") (pinfunction "CC1_A5") (pintype "bidirectional"))
      (node (ref "R2") (pin "2") (pinfunction "2_2") (pintype "passive"))
    )
    (net (code "46") (name "Net-(J1-CC2)") (class "Default")
      (node (ref "J1") (pin "B5") (pinfunction "CC2_B5") (pintype "bidirectional"))
      (node (ref "R1") (pin "2") (pinfunction "2_2") (pintype "passive"))
    )
    (net (code "47") (name "Net-(J1-SHLD-PadSHLD1)") (class "Default")
      (node (ref "J1") (pin "SHLD1") (pinfunction "SHLD_SHLD1") (pintype "bidirectional"))
      (node (ref "J1") (pin "SHLD2") (pinfunction "SHLD_SHLD2") (pintype "bidirectional"))
      (node (ref "J1") (pin "SHLD3") (pinfunction "SHLD_SHLD3") (pintype "bidirectional"))
      (node (ref "J1") (pin "SHLD4") (pinfunction "SHLD_SHLD4") (pintype "bidirectional"))
      (node (ref "SHLD") (pin "2") (pinfunction "2_2") (pintype "passive"))
    )
    (net (code "48") (name "Net-(Q1A-B)") (class "Default")
      (node (ref "Q1") (pin "5") (pinfunction "B_5") (pintype "passive"))
      (node (ref "R4") (pin "1") (pinfunction "1_1") (pintype "passive"))
    )
    (net (code "49") (name "Net-(Q1B-B)") (class "Default")
      (node (ref "Q1") (pin "2") (pinfunction "B_2") (pintype "passive"))
      (node (ref "R5") (pin "1") (pinfunction "1_1") (pintype "passive"))
    )
    (net (code "50") (name "Net-(R6-Pad1)") (class "Default")
      (node (ref "R6") (pin "1") (pinfunction "1_1") (pintype "passive"))
      (node (ref "STAT") (pin "2") (pinfunction "2_2") (pintype "passive"))
    )
    (net (code "51") (name "Net-(U5-PROG)") (class "Default")
      (node (ref "R7") (pin "2") (pinfunction "2_2") (pintype "passive"))
      (node (ref "U5") (pin "5") (pinfunction "PROG_5") (pintype "input"))
    )
    (net (code "52") (name "Net-(U5-STAT)") (class "Default")
      (node (ref "R8") (pin "2") (pinfunction "2_2") (pintype "passive"))
      (node (ref "U5") (pin "1") (pinfunction "STAT_1") (pintype "output"))
      (node (ref "VIN1") (pin "1") (pinfunction "1_1") (pintype "bidirectional"))
    )
    (net (code "53") (name "Net-(U8-CAP)") (class "Default")
      (node (ref "C24") (pin "1") (pinfunction "1_1") (pintype "passive"))
      (node (ref "U8") (pin "10") (pinfunction "CAP_10") (pintype "passive"))
    )
    (net (code "54") (name "PWREN") (class "Default")
      (node (ref "PWREN") (pin "1") (pinfunction "1_1") (pintype "bidirectional"))
      (node (ref "R15") (pin "2") (pinfunction "2_2") (pintype "passive"))
      (node (ref "U10") (pin "12") (pinfunction "4E_12") (pintype "bidirectional"))
      (node (ref "U10") (pin "5") (pinfunction "2E_5") (pintype "bidirectional"))
      (node (ref "U3") (pin "3") (pinfunction "EN_3") (pintype "input"))
      (node (ref "U9") (pin "10") (pinfunction "4Z_10") (pintype "bidirectional"))
      (node (ref "U9") (pin "13") (pinfunction "1E_13") (pintype "bidirectional"))
      (node (ref "U9") (pin "5") (pinfunction "2E_5") (pintype "bidirectional"))
      (node (ref "U9") (pin "6") (pinfunction "3E_6") (pintype "bidirectional"))
    )
    (net (code "55") (name "QWIIC_SCL") (class "Default")
      (node (ref "J10") (pin "4") (pinfunction "4_4") (pintype "passive"))
      (node (ref "J4") (pin "4") (pinfunction "4_4") (pintype "passive"))
      (node (ref "J5") (pin "4") (pinfunction "4_4") (pintype "passive"))
      (node (ref "U10") (pin "10") (pinfunction "4Z_10") (pintype "bidirectional"))
    )
    (net (code "56") (name "QWIIC_SDA") (class "Default")
      (node (ref "J10") (pin "3") (pinfunction "3_3") (pintype "passive"))
      (node (ref "J4") (pin "3") (pinfunction "3_3") (pintype "passive"))
      (node (ref "J5") (pin "3") (pinfunction "3_3") (pintype "passive"))
      (node (ref "U10") (pin "3") (pinfunction "2Z_3") (pintype "bidirectional"))
    )
    (net (code "57") (name "SD_CMD") (class "Default")
      (node (ref "J3") (pin "3") (pinfunction "CMD/SDI_3") (pintype "bidirectional"))
      (node (ref "R10") (pin "1") (pinfunction "1_1") (pintype "passive"))
      (node (ref "U9") (pin "9") (pinfunction "3Z_9") (pintype "bidirectional"))
    )
    (net (code "58") (name "SD_DAT0") (class "Default")
      (node (ref "J3") (pin "7") (pinfunction "DAT0/SDO_7") (pintype "bidirectional"))
      (node (ref "R11") (pin "1") (pinfunction "1_1") (pintype "passive"))
      (node (ref "U9") (pin "2") (pinfunction "1Z_2") (pintype "bidirectional"))
    )
    (net (code "59") (name "SD_DAT2") (class "Default")
      (node (ref "J3") (pin "1") (pinfunction "DAT2_1") (pintype "bidirectional"))
      (node (ref "R13") (pin "1") (pinfunction "1_1") (pintype "passive"))
      (node (ref "U9") (pin "3") (pinfunction "2Z_3") (pintype "bidirectional"))
    )
    (net (code "60") (name "VIN") (class "Default")
      (node (ref "C10") (pin "1") (pinfunction "1_1") (pintype "passive"))
      (node (ref "C12") (pin "1") (pinfunction "1_1") (pintype "passive"))
      (node (ref "C16") (pin "1") (pinfunction "1_1") (pintype "passive"))
      (node (ref "C17") (pin "1") (pinfunction "1_1") (pintype "passive"))
      (node (ref "C29") (pin "1") (pinfunction "1_1") (pintype "passive"))
      (node (ref "C8") (pin "1") (pinfunction "1_1") (pintype "passive"))
      (node (ref "C9") (pin "1") (pinfunction "1_1") (pintype "passive"))
      (node (ref "CHG") (pin "2") (pinfunction "2_2") (pintype "passive"))
      (node (ref "D4") (pin "C") (pinfunction "C_C") (pintype "passive"))
      (node (ref "D5") (pin "C") (pinfunction "C_C") (pintype "passive"))
      (node (ref "D6") (pin "C") (pinfunction "C_C") (pintype "passive"))
      (node (ref "U3") (pin "1") (pinfunction "IN_1") (pintype "input"))
      (node (ref "U5") (pin "4") (pinfunction "VIN_4") (pintype "power_in"))
      (node (ref "U6") (pin "1") (pinfunction "IN_1") (pintype "input"))
      (node (ref "U6") (pin "3") (pinfunction "EN_3") (pintype "input"))
      (node (ref "VIN") (pin "1") (pinfunction "1_1") (pintype "bidirectional"))
    )
    (net (code "61") (name "V_BATT") (class "Default")
      (node (ref "C11") (pin "1") (pinfunction "1_1") (pintype "passive"))
      (node (ref "C13") (pin "1") (pinfunction "1_1") (pintype "passive"))
      (node (ref "C30") (pin "1") (pinfunction "1_1") (pintype "passive"))
      (node (ref "D4") (pin "A") (pinfunction "A_A") (pintype "passive"))
      (node (ref "J2") (pin "2") (pinfunction "+_2") (pintype "bidirectional"))
      (node (ref "J7") (pin "1") (pinfunction "1_1") (pintype "passive"))
      (node (ref "U4") (pin "2") (pinfunction "CELL_2") (pintype "input"))
      (node (ref "U4") (pin "3") (pinfunction "VDD_3") (pintype "bidirectional"))
      (node (ref "U5") (pin "3") (pinfunction "VBAT_3") (pintype "power_in"))
    )
    (net (code "62") (name "V_USB") (class "Default")
      (node (ref "D5") (pin "A") (pinfunction "A_A") (pintype "passive"))
      (node (ref "D7") (pin "2") (pinfunction "C_2") (pintype "passive"))
      (node (ref "J1") (pin "VBUS1") (pinfunction "VBUS_VBUS1") (pintype "bidirectional"))
      (node (ref "J1") (pin "VBUS2") (pinfunction "VBUS_VBUS2") (pintype "bidirectional"))
    )
    (net (code "63") (name "unconnected-(J2-PAD1-PadNC1)") (class "Default")
      (node (ref "J2") (pin "NC1") (pinfunction "PAD1_NC1") (pintype "bidirectional"))
    )
    (net (code "64") (name "unconnected-(J2-PAD2-PadNC2)") (class "Default")
      (node (ref "J2") (pin "NC2") (pinfunction "PAD2_NC2") (pintype "bidirectional"))
    )
    (net (code "65") (name "unconnected-(J3-DET-Pad9)") (class "Default")
      (node (ref "J3") (pin "9") (pinfunction "DET_9") (pintype "bidirectional"))
    )
    (net (code "66") (name "unconnected-(U2-R232-Pad15)") (class "Default")
      (node (ref "U2") (pin "15") (pinfunction "R232_15") (pintype "bidirectional"))
    )
    (net (code "67") (name "unconnected-(U2-~{CTS}-Pad9)") (class "Default")
      (node (ref "U2") (pin "9") (pinfunction "~{CTS}_9") (pintype "bidirectional"))
    )
    (net (code "68") (name "unconnected-(U2-~{DCD}-Pad12)") (class "Default")
      (node (ref "U2") (pin "12") (pinfunction "~{DCD}_12") (pintype "bidirectional"))
    )
    (net (code "69") (name "unconnected-(U2-~{DSR}-Pad10)") (class "Default")
      (node (ref "U2") (pin "10") (pinfunction "~{DSR}_10") (pintype "bidirectional"))
    )
    (net (code "70") (name "unconnected-(U2-~{RI}-Pad11)") (class "Default")
      (node (ref "U2") (pin "11") (pinfunction "~{RI}_11") (pintype "bidirectional"))
    )
    (net (code "71") (name "unconnected-(U4-~{ALRT}-Pad5)") (class "Default")
      (node (ref "U4") (pin "5") (pinfunction "~{ALRT}_5") (pintype "bidirectional"))
    )
    (net (code "72") (name "unconnected-(U7-OCS_AUX-PadP10)") (class "Default")
      (node (ref "U7") (pin "P10") (pinfunction "OCS_AUX_P10") (pintype "bidirectional"))
    )
    (net (code "73") (name "unconnected-(U7-SDO_AUX-PadP11)") (class "Default")
      (node (ref "U7") (pin "P11") (pinfunction "SDO_AUX_P11") (pintype "bidirectional"))
    )
    (net (code "74") (name "unconnected-(U10-1Y-Pad1)") (class "Default")
      (node (ref "U10") (pin "1") (pinfunction "1Y_1") (pintype "bidirectional"))
    )
    (net (code "75") (name "unconnected-(U10-1Z-Pad2)") (class "Default")
      (node (ref "U10") (pin "2") (pinfunction "1Z_2") (pintype "bidirectional"))
    )
    (net (code "76") (name "unconnected-(U10-3Y-Pad8)") (class "Default")
      (node (ref "U10") (pin "8") (pinfunction "3Y_8") (pintype "bidirectional"))
    )
    (net (code "77") (name "unconnected-(U10-3Z-Pad9)") (class "Default")
      (node (ref "U10") (pin "9") (pinfunction "3Z_9") (pintype "bidirectional"))
    )
  )
)
